# MPU6050_v2.net
KiCad netlist of a schematic drawn in Altium Designer
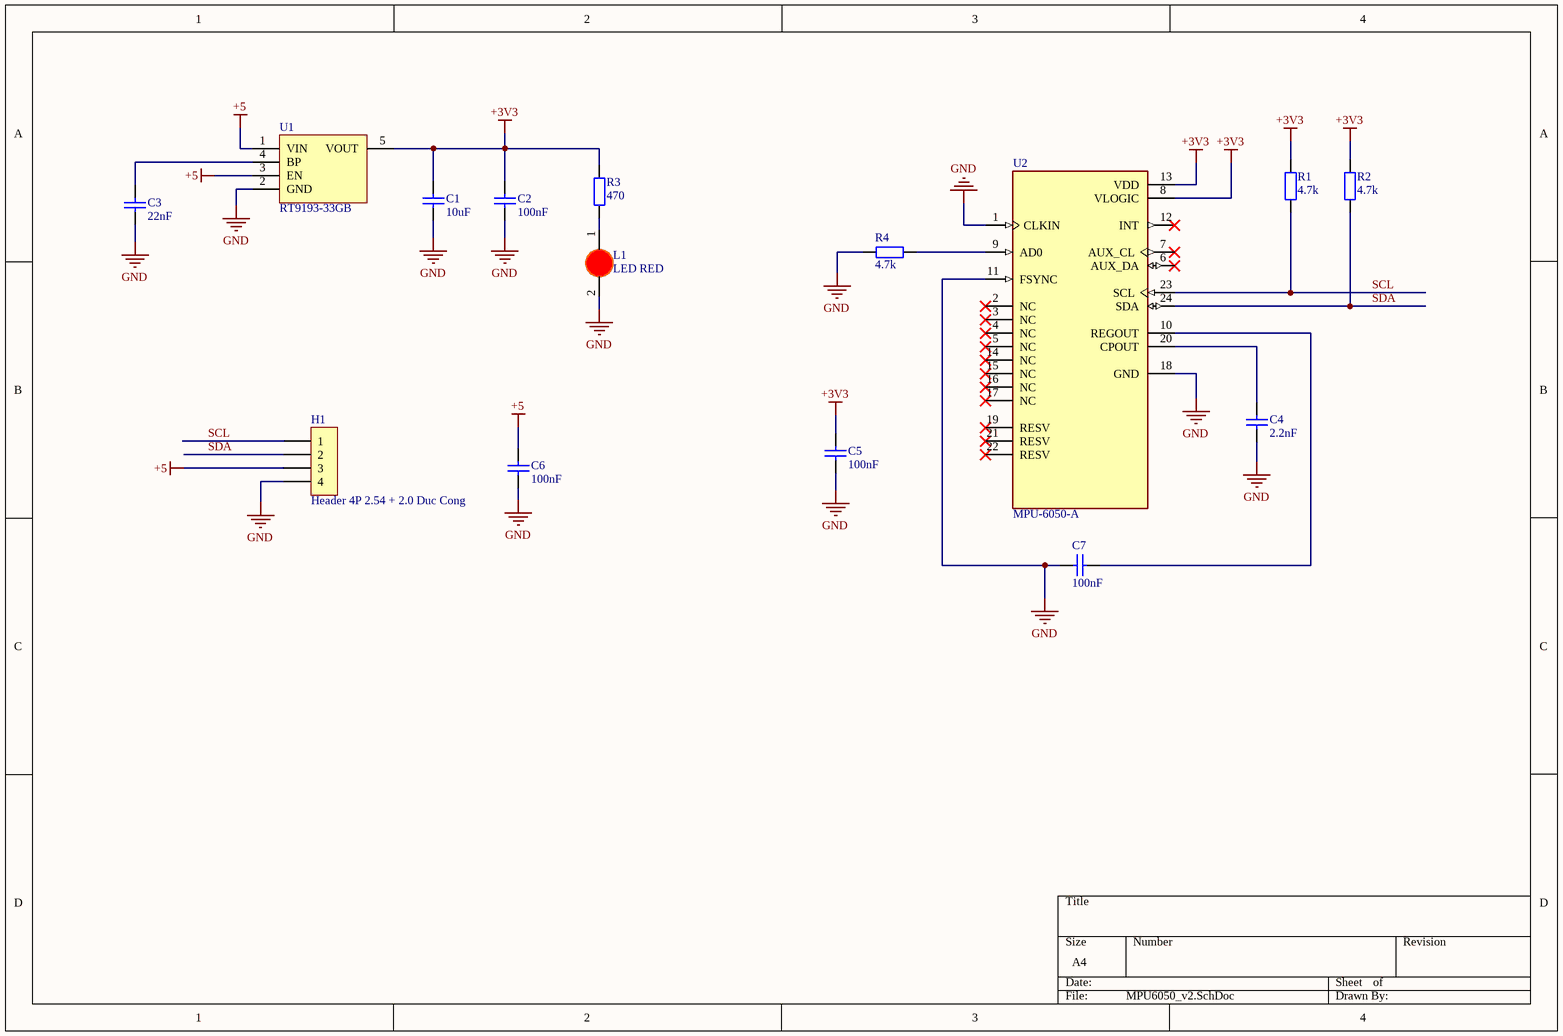
[diagram p0: MPU6050_v2.SchDoc]

(export (version "E")
  (design (tool "Eeschema 10.0.6"))
  (components
    (comp (ref "C1")
      (value "10uF")
      (footprint "tu 0603")
      (description "Dán")
      (libsource (lib "namnt_Lib") (part "Tu 0603 106 16V 20%"))
    )
    (comp (ref "C2")
      (value "100nF")
      (footprint "tu 0603")
      (description "Dán")
      (libsource (lib "namnt_Lib") (part "Tu 0603 104 50V 10%"))
    )
    (comp (ref "C3")
      (value "22nF")
      (footprint "tu 0603")
      (description "Dán")
      (libsource (lib "namnt_Lib") (part "Tu 0603 104 50V 10%"))
    )
    (comp (ref "C4")
      (value "2.2nF")
      (footprint "tu 0603")
      (description "Dán")
      (libsource (lib "namnt_Lib") (part "Tu 0603 104 50V 10%"))
    )
    (comp (ref "C5")
      (value "100nF")
      (footprint "tu 0603")
      (description "Dán")
      (libsource (lib "namnt_Lib") (part "Tu 0603 104 50V 10%"))
    )
    (comp (ref "C6")
      (value "100nF")
      (footprint "tu 0603")
      (description "Dán")
      (libsource (lib "namnt_Lib") (part "Tu 0603 104 50V 10%"))
    )
    (comp (ref "C7")
      (value "100nF")
      (footprint "tu 0603")
      (description "Dán")
      (libsource (lib "namnt_Lib") (part "Tu 0603 104 50V 10%"))
    )
    (comp (ref "H1")
      (value "Header 4P 2.54 + 2.0 Duc Cong")
      (footprint "Header 4P DC 2.54 + 2.0")
      (description "Cắm")
      (libsource (lib "namnt_Lib") (part "Header 4P 2.54 + 2.0 Duc Cong"))
    )
    (comp (ref "L1")
      (value "LED RED")
      (footprint "LED-0805-Red")
      (description "Dán")
      (libsource (lib "namnt_Lib") (part "LED 0805 Do"))
    )
    (comp (ref "R1")
      (value "4.7k")
      (footprint "tro smd 0603")
      (description "Dán")
      (libsource (lib "namnt_Lib") (part "Tro 0603 5% 4.7k"))
    )
    (comp (ref "R2")
      (value "4.7k")
      (footprint "tro smd 0603")
      (description "Dán")
      (libsource (lib "namnt_Lib") (part "Tro 0603 5% 4.7k"))
    )
    (comp (ref "R3")
      (value "470")
      (footprint "tro smd 0603")
      (description "Dán")
      (libsource (lib "namnt_Lib") (part "Tro 0603 1% 1k"))
    )
    (comp (ref "R4")
      (value "4.7k")
      (footprint "tro smd 0603")
      (description "Dán")
      (libsource (lib "namnt_Lib") (part "Tro 0603 5% 4.7k"))
    )
    (comp (ref "U1")
      (value "RT9193-33GB")
      (footprint "SOT23-5")
      (description "Linear Voltage Regulator IC 1 Output 300mA SOT-23-5")
      (fields (field (name "MANUFACTURER") "Richtek USA Inc."))
      (libsource (lib "namnt_Lib") (part "REG_5.5V-3.3V-0.3A-1W-SOT-23-5"))
    )
    (comp (ref "U2")
      (value "MPU-6050-A")
      (footprint "QFN50P400X400X95-24N")
      (fields (field (name "MF") "TDK InvenSense"))
      (libsource (lib "namnt_Lib") (part "MPU-6050-A"))
    )
  )
  (nets
    (net (code "1") (name "+3V3") (class "Default")
      (node (ref "C1") (pin "1") (pinfunction "1_1") (pintype "passive"))
      (node (ref "C2") (pin "1") (pinfunction "1_1") (pintype "passive"))
      (node (ref "C5") (pin "1") (pinfunction "1_1") (pintype "passive"))
      (node (ref "R1") (pin "2") (pinfunction "2_2") (pintype "passive"))
      (node (ref "R2") (pin "2") (pinfunction "2_2") (pintype "passive"))
      (node (ref "R3") (pin "2") (pinfunction "2_2") (pintype "passive"))
      (node (ref "U1") (pin "5") (pinfunction "VOUT_5") (pintype "passive"))
      (node (ref "U2") (pin "13") (pinfunction "VDD_13") (pintype "power_in"))
      (node (ref "U2") (pin "8") (pinfunction "VLOGIC_8") (pintype "power_in"))
    )
    (net (code "2") (name "+5") (class "Default")
      (node (ref "C6") (pin "1") (pinfunction "1_1") (pintype "passive"))
      (node (ref "H1") (pin "3") (pinfunction "3_3") (pintype "passive"))
      (node (ref "U1") (pin "1") (pinfunction "VIN_1") (pintype "passive"))
      (node (ref "U1") (pin "3") (pinfunction "EN_3") (pintype "passive"))
    )
    (net (code "3") (name "/SCL") (class "Default")
      (node (ref "H1") (pin "1") (pinfunction "1_1") (pintype "passive"))
      (node (ref "R1") (pin "1") (pinfunction "1_1") (pintype "passive"))
      (node (ref "U2") (pin "23") (pinfunction "SCL_23") (pintype "input"))
    )
    (net (code "4") (name "/SDA") (class "Default")
      (node (ref "H1") (pin "2") (pinfunction "2_2") (pintype "passive"))
      (node (ref "R2") (pin "1") (pinfunction "1_1") (pintype "passive"))
      (node (ref "U2") (pin "24") (pinfunction "SDA_24") (pintype "bidirectional"))
    )
    (net (code "5") (name "GND") (class "Default")
      (node (ref "C1") (pin "2") (pinfunction "2_2") (pintype "passive"))
      (node (ref "C2") (pin "2") (pinfunction "2_2") (pintype "passive"))
      (node (ref "C3") (pin "2") (pinfunction "2_2") (pintype "passive"))
      (node (ref "C4") (pin "2") (pinfunction "2_2") (pintype "passive"))
      (node (ref "C5") (pin "2") (pinfunction "2_2") (pintype "passive"))
      (node (ref "C6") (pin "2") (pinfunction "2_2") (pintype "passive"))
      (node (ref "C7") (pin "1") (pinfunction "1_1") (pintype "passive"))
      (node (ref "H1") (pin "4") (pinfunction "4_4") (pintype "passive"))
      (node (ref "L1") (pin "2") (pinfunction "K_2") (pintype "passive"))
      (node (ref "R4") (pin "2") (pinfunction "2_2") (pintype "passive"))
      (node (ref "U1") (pin "2") (pinfunction "GND_2") (pintype "passive"))
      (node (ref "U2") (pin "1") (pinfunction "CLKIN_1") (pintype "input"))
      (node (ref "U2") (pin "11") (pinfunction "FSYNC_11") (pintype "input"))
      (node (ref "U2") (pin "18") (pinfunction "GND_18") (pintype "power_in"))
    )
    (net (code "6") (name "Net-(L1-A)") (class "Default")
      (node (ref "L1") (pin "1") (pinfunction "A_1") (pintype "passive"))
      (node (ref "R3") (pin "1") (pinfunction "1_1") (pintype "passive"))
    )
    (net (code "7") (name "Net-(U1-BP)") (class "Default")
      (node (ref "C3") (pin "1") (pinfunction "1_1") (pintype "passive"))
      (node (ref "U1") (pin "4") (pinfunction "BP_4") (pintype "passive"))
    )
    (net (code "8") (name "Net-(U2-AD0)") (class "Default")
      (node (ref "R4") (pin "1") (pinfunction "1_1") (pintype "passive"))
      (node (ref "U2") (pin "9") (pinfunction "AD0_9") (pintype "input"))
    )
    (net (code "9") (name "Net-(U2-CPOUT)") (class "Default")
      (node (ref "C4") (pin "1") (pinfunction "1_1") (pintype "passive"))
      (node (ref "U2") (pin "20") (pinfunction "CPOUT_20") (pintype "passive"))
    )
    (net (code "10") (name "Net-(U2-REGOUT)") (class "Default")
      (node (ref "C7") (pin "2") (pinfunction "2_2") (pintype "passive"))
      (node (ref "U2") (pin "10") (pinfunction "REGOUT_10") (pintype "passive"))
    )
    (net (code "11") (name "unconnected-(U2-AUX_CL-Pad7)") (class "Default")
      (node (ref "U2") (pin "7") (pinfunction "AUX_CL_7") (pintype "output+no_connect"))
    )
    (net (code "12") (name "unconnected-(U2-AUX_DA-Pad6)") (class "Default")
      (node (ref "U2") (pin "6") (pinfunction "AUX_DA_6") (pintype "bidirectional+no_connect"))
    )
    (net (code "13") (name "unconnected-(U2-INT-Pad12)") (class "Default")
      (node (ref "U2") (pin "12") (pinfunction "INT_12") (pintype "output+no_connect"))
    )
    (net (code "14") (name "unconnected-(U2-NC-Pad2)") (class "Default")
      (node (ref "U2") (pin "2") (pinfunction "NC_2") (pintype "passive+no_connect"))
    )
    (net (code "15") (name "unconnected-(U2-NC-Pad3)") (class "Default")
      (node (ref "U2") (pin "3") (pinfunction "NC_3") (pintype "passive+no_connect"))
    )
    (net (code "16") (name "unconnected-(U2-NC-Pad4)") (class "Default")
      (node (ref "U2") (pin "4") (pinfunction "NC_4") (pintype "passive+no_connect"))
    )
    (net (code "17") (name "unconnected-(U2-NC-Pad5)") (class "Default")
      (node (ref "U2") (pin "5") (pinfunction "NC_5") (pintype "passive+no_connect"))
    )
    (net (code "18") (name "unconnected-(U2-NC-Pad14)") (class "Default")
      (node (ref "U2") (pin "14") (pinfunction "NC_14") (pintype "passive+no_connect"))
    )
    (net (code "19") (name "unconnected-(U2-NC-Pad15)") (class "Default")
      (node (ref "U2") (pin "15") (pinfunction "NC_15") (pintype "passive+no_connect"))
    )
    (net (code "20") (name "unconnected-(U2-NC-Pad16)") (class "Default")
      (node (ref "U2") (pin "16") (pinfunction "NC_16") (pintype "passive+no_connect"))
    )
    (net (code "21") (name "unconnected-(U2-NC-Pad17)") (class "Default")
      (node (ref "U2") (pin "17") (pinfunction "NC_17") (pintype "passive+no_connect"))
    )
    (net (code "22") (name "unconnected-(U2-RESV-Pad19)") (class "Default")
      (node (ref "U2") (pin "19") (pinfunction "RESV_19") (pintype "passive+no_connect"))
    )
    (net (code "23") (name "unconnected-(U2-RESV-Pad21)") (class "Default")
      (node (ref "U2") (pin "21") (pinfunction "RESV_21") (pintype "passive+no_connect"))
    )
    (net (code "24") (name "unconnected-(U2-RESV-Pad22)") (class "Default")
      (node (ref "U2") (pin "22") (pinfunction "RESV_22") (pintype "passive+no_connect"))
    )
  )
)
